# SH12_-_RS-485.net
KiCad netlist of a schematic drawn in Altium Designer
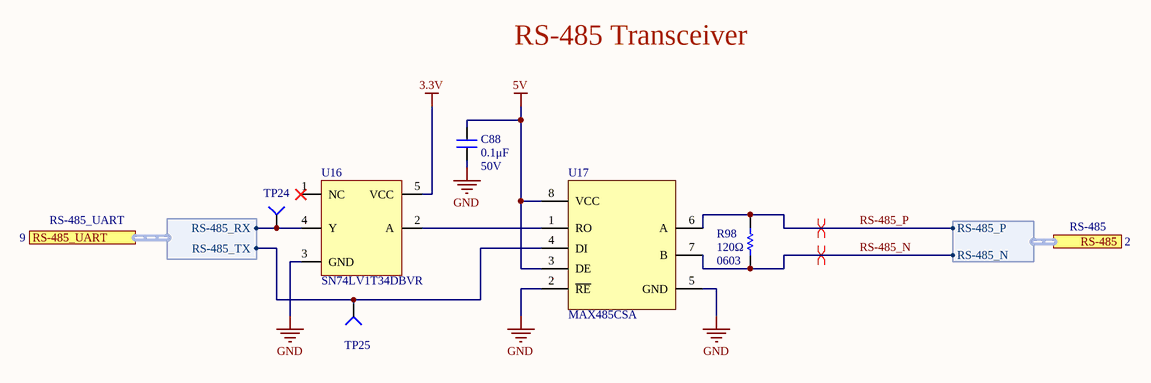
[diagram p0: SH12 - RS-485.SchDoc]

(export (version "E")
  (design (tool "Eeschema 10.0.6"))
  (components
    (comp (ref "C88")
      (value "0.1μF")
      (footprint "CAP0603")
      (description "CAP CER 0.1UF 50V X7R 0603")
      (fields (field (name "VOLTAGE RATING") "50V") (field (name "Comment") "CAP_0.1uF_50V_0603"))
      (libsource (lib "UWRT_Schematic_Library_2020") (part "CAP_0.1uF_50V_0603"))
    )
    (comp (ref "R98")
      (value "120Ω")
      (footprint "RESC0603(1608)_N")
      (description "RES 120 OHM 5% 1/10W 0603")
      (fields
        (field (name "TOLERANCE") "5%")
        (field (name "CASE CODE (IMPERIAL)") "0603")
        (field (name "Comment") "RES_120Ω_0603")
      )
      (libsource (lib "UWRT_Schematic_Library_2020") (part "RES_120Ω_0603_5%"))
    )
    (comp (ref "TP24")
      (value "TESTPOINT_SMD_LOOP")
      (footprint "S1751-46R")
      (description "PC TEST POINT SMD")
      (libsource (lib "UWRT_Schematic_Library_2020") (part "TESTPOINT_SMD_LOOP"))
    )
    (comp (ref "TP25")
      (value "TESTPOINT_SMD_LOOP")
      (footprint "S1751-46R")
      (description "PC TEST POINT SMD")
      (libsource (lib "UWRT_Schematic_Library_2020") (part "TESTPOINT_SMD_LOOP"))
    )
    (comp (ref "U16")
      (value "SN74LV1T34")
      (footprint "SN74LV1T34DBVR")
      (description "Bus Driver, LV/LV-A/LVX/H Series, 1-Func, 1-Bit, True Output, CMOS, PDSO5")
      (fields (field (name "MANUFACTURER PART NUMBER 1") "SN74LV1T34DBVR"))
      (libsource (lib "UWRT_Schematic_Library_2020") (part "SN74LV1T34"))
    )
    (comp (ref "U17")
      (value "MAX485CSA")
      (footprint "SOIC127P600X175-8N")
      (description "1/1 Transceiver Half RS422, RS485 8-SOIC")
      (libsource (lib "UWRT_Schematic_Library_2020") (part "MAX485CSA"))
    )
  )
  (nets
    (net (code "3") (name "/RS-485_N") (class "Default")
      (node (ref "R98") (pin "1") (pinfunction "1_1") (pintype "passive"))
      (node (ref "U17") (pin "7") (pinfunction "B_7") (pintype "passive"))
    )
    (net (code "4") (name "/RS-485_P") (class "Default")
      (node (ref "R98") (pin "2") (pinfunction "2_2") (pintype "passive"))
      (node (ref "U17") (pin "6") (pinfunction "A_6") (pintype "passive"))
    )
    (net (code "7") (name "3.3V") (class "Default")
      (node (ref "U16") (pin "5") (pinfunction "VCC_5") (pintype "passive"))
    )
    (net (code "8") (name "5V") (class "Default")
      (node (ref "C88") (pin "1") (pinfunction "1_1") (pintype "passive"))
      (node (ref "U17") (pin "3") (pinfunction "DE_3") (pintype "passive"))
      (node (ref "U17") (pin "8") (pinfunction "VCC_8") (pintype "power_in"))
    )
    (net (code "9") (name "GND") (class "Default")
      (node (ref "C88") (pin "2") (pinfunction "2_2") (pintype "passive"))
      (node (ref "U16") (pin "3") (pinfunction "GND_3") (pintype "passive"))
      (node (ref "U17") (pin "2") (pinfunction "~{RE}_2") (pintype "passive"))
      (node (ref "U17") (pin "5") (pinfunction "GND_5") (pintype "power_in"))
    )
    (net (code "10") (name "Net-(TP24-=value)") (class "Default")
      (node (ref "TP24") (pin "1") (pinfunction "=value_1") (pintype "passive"))
      (node (ref "U16") (pin "4") (pinfunction "Y_4") (pintype "passive"))
    )
    (net (code "11") (name "Net-(TP25-=value)") (class "Default")
      (node (ref "TP25") (pin "1") (pinfunction "=value_1") (pintype "passive"))
      (node (ref "U17") (pin "4") (pinfunction "DI_4") (pintype "passive"))
    )
    (net (code "12") (name "Net-(U16-A)") (class "Default")
      (node (ref "U16") (pin "2") (pinfunction "A_2") (pintype "passive"))
      (node (ref "U17") (pin "1") (pinfunction "RO_1") (pintype "passive"))
    )
    (net (code "13") (name "unconnected-(U16-NC-Pad1)") (class "Default")
      (node (ref "U16") (pin "1") (pinfunction "NC_1") (pintype "passive+no_connect"))
    )
  )
)
